# 8HA.net
KiCad netlist of a schematic drawn in EAGLE
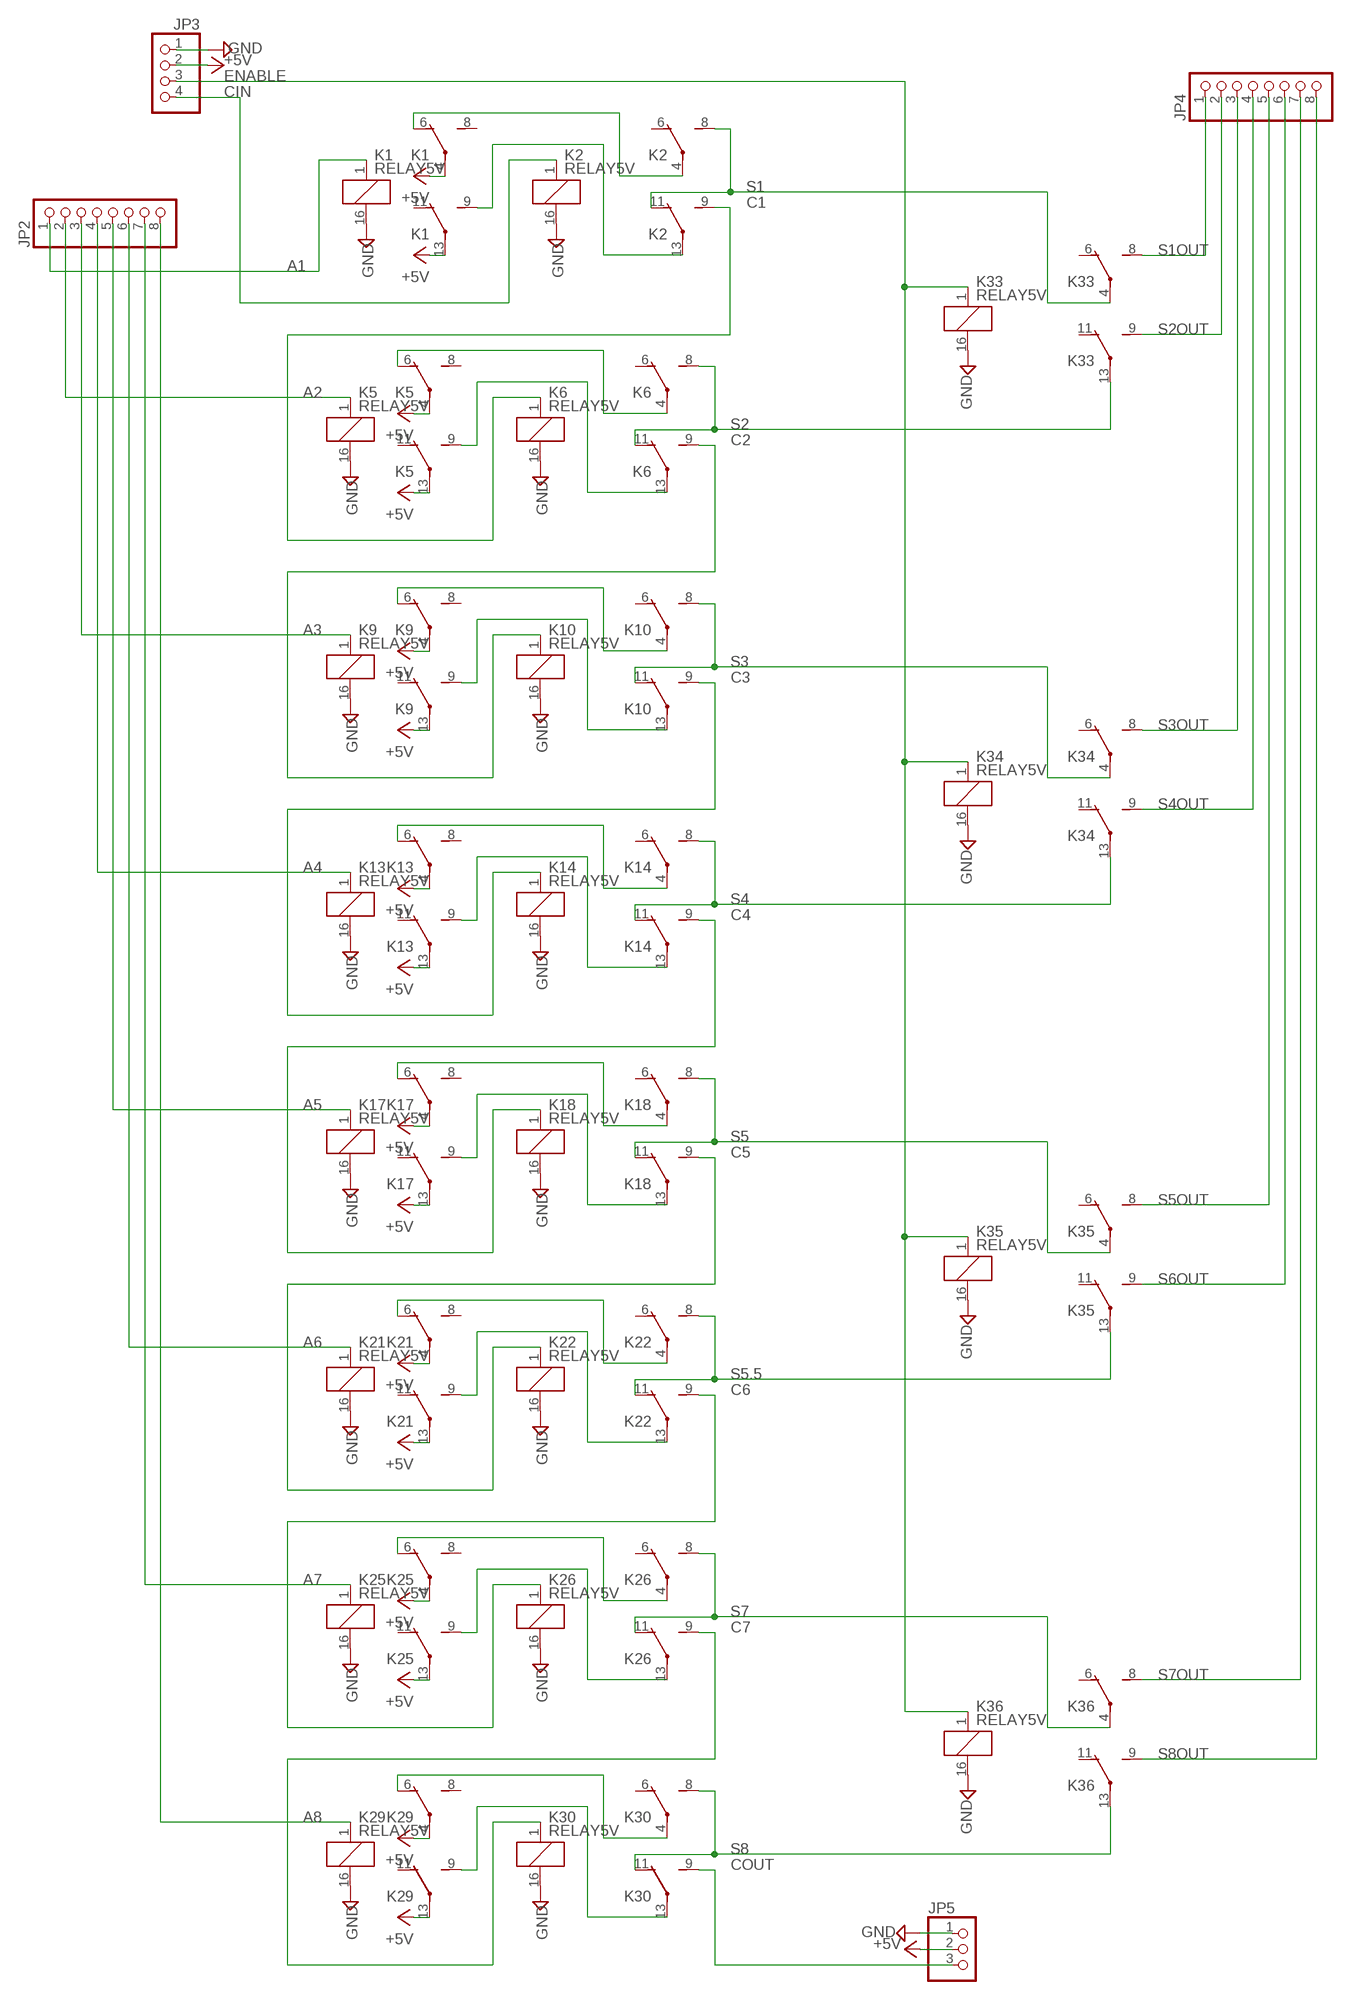
[diagram p0: schematic, sheet 1]

(export (version "E")
  (design (tool "Eeschema 10.0.6"))
  (components
    (comp (ref "JP2")
      (value "PINHD-1X8")
      (footprint "eagle-import:1X08")
      (libsource (lib "eagle-import") (part "PINHD-1X8"))
    )
    (comp (ref "JP3")
      (value "PINHD-1X4")
      (footprint "eagle-import:1X04")
      (libsource (lib "eagle-import") (part "PINHD-1X4"))
    )
    (comp (ref "JP4")
      (value "PINHD-1X8")
      (footprint "eagle-import:1X08")
      (libsource (lib "eagle-import") (part "PINHD-1X8"))
    )
    (comp (ref "JP5")
      (value "PINHD-1X3")
      (footprint "eagle-import:1X03")
      (libsource (lib "eagle-import") (part "PINHD-1X3"))
    )
    (comp (ref "K1")
      (value "RELAY5V")
      (footprint "eagle-import:DS-BT")
      (libsource (lib "eagle-import") (part "RELAY5V"))
    )
    (comp (ref "K2")
      (value "RELAY5V")
      (footprint "eagle-import:DS-BT")
      (libsource (lib "eagle-import") (part "RELAY5V"))
    )
    (comp (ref "K5")
      (value "RELAY5V")
      (footprint "eagle-import:DS-BT")
      (libsource (lib "eagle-import") (part "RELAY5V"))
    )
    (comp (ref "K6")
      (value "RELAY5V")
      (footprint "eagle-import:DS-BT")
      (libsource (lib "eagle-import") (part "RELAY5V"))
    )
    (comp (ref "K9")
      (value "RELAY5V")
      (footprint "eagle-import:DS-BT")
      (libsource (lib "eagle-import") (part "RELAY5V"))
    )
    (comp (ref "K10")
      (value "RELAY5V")
      (footprint "eagle-import:DS-BT")
      (libsource (lib "eagle-import") (part "RELAY5V"))
    )
    (comp (ref "K13")
      (value "RELAY5V")
      (footprint "eagle-import:DS-BT")
      (libsource (lib "eagle-import") (part "RELAY5V"))
    )
    (comp (ref "K14")
      (value "RELAY5V")
      (footprint "eagle-import:DS-BT")
      (libsource (lib "eagle-import") (part "RELAY5V"))
    )
    (comp (ref "K17")
      (value "RELAY5V")
      (footprint "eagle-import:DS-BT")
      (libsource (lib "eagle-import") (part "RELAY5V"))
    )
    (comp (ref "K18")
      (value "RELAY5V")
      (footprint "eagle-import:DS-BT")
      (libsource (lib "eagle-import") (part "RELAY5V"))
    )
    (comp (ref "K21")
      (value "RELAY5V")
      (footprint "eagle-import:DS-BT")
      (libsource (lib "eagle-import") (part "RELAY5V"))
    )
    (comp (ref "K22")
      (value "RELAY5V")
      (footprint "eagle-import:DS-BT")
      (libsource (lib "eagle-import") (part "RELAY5V"))
    )
    (comp (ref "K25")
      (value "RELAY5V")
      (footprint "eagle-import:DS-BT")
      (libsource (lib "eagle-import") (part "RELAY5V"))
    )
    (comp (ref "K26")
      (value "RELAY5V")
      (footprint "eagle-import:DS-BT")
      (libsource (lib "eagle-import") (part "RELAY5V"))
    )
    (comp (ref "K29")
      (value "RELAY5V")
      (footprint "eagle-import:DS-BT")
      (libsource (lib "eagle-import") (part "RELAY5V"))
    )
    (comp (ref "K30")
      (value "RELAY5V")
      (footprint "eagle-import:DS-BT")
      (libsource (lib "eagle-import") (part "RELAY5V"))
    )
    (comp (ref "K33")
      (value "RELAY5V")
      (footprint "eagle-import:DS-BT")
      (libsource (lib "eagle-import") (part "RELAY5V"))
    )
    (comp (ref "K34")
      (value "RELAY5V")
      (footprint "eagle-import:DS-BT")
      (libsource (lib "eagle-import") (part "RELAY5V"))
    )
    (comp (ref "K35")
      (value "RELAY5V")
      (footprint "eagle-import:DS-BT")
      (libsource (lib "eagle-import") (part "RELAY5V"))
    )
    (comp (ref "K36")
      (value "RELAY5V")
      (footprint "eagle-import:DS-BT")
      (libsource (lib "eagle-import") (part "RELAY5V"))
    )
  )
  (nets
    (net (code "1") (name "+5V") (class "Default")
      (node (ref "JP3") (pin "2") (pinfunction "2_2") (pintype "passive"))
      (node (ref "JP5") (pin "2") (pinfunction "2_2") (pintype "passive"))
      (node (ref "K1") (pin "13") (pinfunction "P_13") (pintype "passive"))
      (node (ref "K1") (pin "4") (pinfunction "P_4") (pintype "passive"))
      (node (ref "K13") (pin "13") (pinfunction "P_13") (pintype "passive"))
      (node (ref "K13") (pin "4") (pinfunction "P_4") (pintype "passive"))
      (node (ref "K17") (pin "13") (pinfunction "P_13") (pintype "passive"))
      (node (ref "K17") (pin "4") (pinfunction "P_4") (pintype "passive"))
      (node (ref "K21") (pin "13") (pinfunction "P_13") (pintype "passive"))
      (node (ref "K21") (pin "4") (pinfunction "P_4") (pintype "passive"))
      (node (ref "K25") (pin "13") (pinfunction "P_13") (pintype "passive"))
      (node (ref "K25") (pin "4") (pinfunction "P_4") (pintype "passive"))
      (node (ref "K29") (pin "13") (pinfunction "P_13") (pintype "passive"))
      (node (ref "K29") (pin "4") (pinfunction "P_4") (pintype "passive"))
      (node (ref "K5") (pin "13") (pinfunction "P_13") (pintype "passive"))
      (node (ref "K5") (pin "4") (pinfunction "P_4") (pintype "passive"))
      (node (ref "K9") (pin "13") (pinfunction "P_13") (pintype "passive"))
      (node (ref "K9") (pin "4") (pinfunction "P_4") (pintype "passive"))
    )
    (net (code "2") (name "/A1") (class "Default")
      (node (ref "JP2") (pin "1") (pinfunction "1_1") (pintype "passive"))
      (node (ref "K1") (pin "1") (pinfunction "+_1") (pintype "passive"))
    )
    (net (code "3") (name "/A2") (class "Default")
      (node (ref "JP2") (pin "2") (pinfunction "2_2") (pintype "passive"))
      (node (ref "K5") (pin "1") (pinfunction "+_1") (pintype "passive"))
    )
    (net (code "4") (name "/A3") (class "Default")
      (node (ref "JP2") (pin "3") (pinfunction "3_3") (pintype "passive"))
      (node (ref "K9") (pin "1") (pinfunction "+_1") (pintype "passive"))
    )
    (net (code "5") (name "/A4") (class "Default")
      (node (ref "JP2") (pin "4") (pinfunction "4_4") (pintype "passive"))
      (node (ref "K13") (pin "1") (pinfunction "+_1") (pintype "passive"))
    )
    (net (code "6") (name "/A5") (class "Default")
      (node (ref "JP2") (pin "5") (pinfunction "5_5") (pintype "passive"))
      (node (ref "K17") (pin "1") (pinfunction "+_1") (pintype "passive"))
    )
    (net (code "7") (name "/A6") (class "Default")
      (node (ref "JP2") (pin "6") (pinfunction "6_6") (pintype "passive"))
      (node (ref "K21") (pin "1") (pinfunction "+_1") (pintype "passive"))
    )
    (net (code "8") (name "/A7") (class "Default")
      (node (ref "JP2") (pin "7") (pinfunction "7_7") (pintype "passive"))
      (node (ref "K25") (pin "1") (pinfunction "+_1") (pintype "passive"))
    )
    (net (code "9") (name "/A8") (class "Default")
      (node (ref "JP2") (pin "8") (pinfunction "8_8") (pintype "passive"))
      (node (ref "K29") (pin "1") (pinfunction "+_1") (pintype "passive"))
    )
    (net (code "10") (name "/C1") (class "Default")
      (node (ref "K2") (pin "9") (pinfunction "S_9") (pintype "passive"))
      (node (ref "K6") (pin "1") (pinfunction "+_1") (pintype "passive"))
    )
    (net (code "11") (name "/C2") (class "Default")
      (node (ref "K10") (pin "1") (pinfunction "+_1") (pintype "passive"))
      (node (ref "K6") (pin "9") (pinfunction "S_9") (pintype "passive"))
    )
    (net (code "12") (name "/C3") (class "Default")
      (node (ref "K10") (pin "9") (pinfunction "S_9") (pintype "passive"))
      (node (ref "K14") (pin "1") (pinfunction "+_1") (pintype "passive"))
    )
    (net (code "13") (name "/C4") (class "Default")
      (node (ref "K14") (pin "9") (pinfunction "S_9") (pintype "passive"))
      (node (ref "K18") (pin "1") (pinfunction "+_1") (pintype "passive"))
    )
    (net (code "14") (name "/C5") (class "Default")
      (node (ref "K18") (pin "9") (pinfunction "S_9") (pintype "passive"))
      (node (ref "K22") (pin "1") (pinfunction "+_1") (pintype "passive"))
    )
    (net (code "15") (name "/C6") (class "Default")
      (node (ref "K22") (pin "9") (pinfunction "S_9") (pintype "passive"))
      (node (ref "K26") (pin "1") (pinfunction "+_1") (pintype "passive"))
    )
    (net (code "16") (name "/C7") (class "Default")
      (node (ref "K26") (pin "9") (pinfunction "S_9") (pintype "passive"))
      (node (ref "K30") (pin "1") (pinfunction "+_1") (pintype "passive"))
    )
    (net (code "17") (name "/CIN") (class "Default")
      (node (ref "JP3") (pin "4") (pinfunction "4_4") (pintype "passive"))
      (node (ref "K2") (pin "1") (pinfunction "+_1") (pintype "passive"))
    )
    (net (code "18") (name "/COUT") (class "Default")
      (node (ref "JP5") (pin "3") (pinfunction "3_3") (pintype "passive"))
      (node (ref "K30") (pin "9") (pinfunction "S_9") (pintype "passive"))
    )
    (net (code "19") (name "/ENABLE") (class "Default")
      (node (ref "JP3") (pin "3") (pinfunction "3_3") (pintype "passive"))
      (node (ref "K33") (pin "1") (pinfunction "+_1") (pintype "passive"))
      (node (ref "K34") (pin "1") (pinfunction "+_1") (pintype "passive"))
      (node (ref "K35") (pin "1") (pinfunction "+_1") (pintype "passive"))
      (node (ref "K36") (pin "1") (pinfunction "+_1") (pintype "passive"))
    )
    (net (code "20") (name "/S1") (class "Default")
      (node (ref "K2") (pin "11") (pinfunction "O_11") (pintype "passive"))
      (node (ref "K2") (pin "8") (pinfunction "S_8") (pintype "passive"))
      (node (ref "K33") (pin "4") (pinfunction "P_4") (pintype "passive"))
    )
    (net (code "21") (name "/S1OUT") (class "Default")
      (node (ref "JP4") (pin "1") (pinfunction "1_1") (pintype "passive"))
      (node (ref "K33") (pin "8") (pinfunction "S_8") (pintype "passive"))
    )
    (net (code "22") (name "/S2") (class "Default")
      (node (ref "K33") (pin "13") (pinfunction "P_13") (pintype "passive"))
      (node (ref "K6") (pin "11") (pinfunction "O_11") (pintype "passive"))
      (node (ref "K6") (pin "8") (pinfunction "S_8") (pintype "passive"))
    )
    (net (code "23") (name "/S2OUT") (class "Default")
      (node (ref "JP4") (pin "2") (pinfunction "2_2") (pintype "passive"))
      (node (ref "K33") (pin "9") (pinfunction "S_9") (pintype "passive"))
    )
    (net (code "24") (name "/S3") (class "Default")
      (node (ref "K10") (pin "11") (pinfunction "O_11") (pintype "passive"))
      (node (ref "K10") (pin "8") (pinfunction "S_8") (pintype "passive"))
      (node (ref "K34") (pin "4") (pinfunction "P_4") (pintype "passive"))
    )
    (net (code "25") (name "/S3OUT") (class "Default")
      (node (ref "JP4") (pin "3") (pinfunction "3_3") (pintype "passive"))
      (node (ref "K34") (pin "8") (pinfunction "S_8") (pintype "passive"))
    )
    (net (code "26") (name "/S4") (class "Default")
      (node (ref "K14") (pin "11") (pinfunction "O_11") (pintype "passive"))
      (node (ref "K14") (pin "8") (pinfunction "S_8") (pintype "passive"))
      (node (ref "K34") (pin "13") (pinfunction "P_13") (pintype "passive"))
    )
    (net (code "27") (name "/S4OUT") (class "Default")
      (node (ref "JP4") (pin "4") (pinfunction "4_4") (pintype "passive"))
      (node (ref "K34") (pin "9") (pinfunction "S_9") (pintype "passive"))
    )
    (net (code "28") (name "/S5") (class "Default")
      (node (ref "K18") (pin "11") (pinfunction "O_11") (pintype "passive"))
      (node (ref "K18") (pin "8") (pinfunction "S_8") (pintype "passive"))
      (node (ref "K35") (pin "4") (pinfunction "P_4") (pintype "passive"))
    )
    (net (code "29") (name "/S5.5") (class "Default")
      (node (ref "K22") (pin "11") (pinfunction "O_11") (pintype "passive"))
      (node (ref "K22") (pin "8") (pinfunction "S_8") (pintype "passive"))
      (node (ref "K35") (pin "13") (pinfunction "P_13") (pintype "passive"))
    )
    (net (code "30") (name "/S5OUT") (class "Default")
      (node (ref "JP4") (pin "5") (pinfunction "5_5") (pintype "passive"))
      (node (ref "K35") (pin "8") (pinfunction "S_8") (pintype "passive"))
    )
    (net (code "31") (name "/S6OUT") (class "Default")
      (node (ref "JP4") (pin "6") (pinfunction "6_6") (pintype "passive"))
      (node (ref "K35") (pin "9") (pinfunction "S_9") (pintype "passive"))
    )
    (net (code "32") (name "/S7") (class "Default")
      (node (ref "K26") (pin "11") (pinfunction "O_11") (pintype "passive"))
      (node (ref "K26") (pin "8") (pinfunction "S_8") (pintype "passive"))
      (node (ref "K36") (pin "4") (pinfunction "P_4") (pintype "passive"))
    )
    (net (code "33") (name "/S7OUT") (class "Default")
      (node (ref "JP4") (pin "7") (pinfunction "7_7") (pintype "passive"))
      (node (ref "K36") (pin "8") (pinfunction "S_8") (pintype "passive"))
    )
    (net (code "34") (name "/S8") (class "Default")
      (node (ref "K30") (pin "11") (pinfunction "O_11") (pintype "passive"))
      (node (ref "K30") (pin "8") (pinfunction "S_8") (pintype "passive"))
      (node (ref "K36") (pin "13") (pinfunction "P_13") (pintype "passive"))
    )
    (net (code "35") (name "/S8OUT") (class "Default")
      (node (ref "JP4") (pin "8") (pinfunction "8_8") (pintype "passive"))
      (node (ref "K36") (pin "9") (pinfunction "S_9") (pintype "passive"))
    )
    (net (code "36") (name "GND") (class "Default")
      (node (ref "JP3") (pin "1") (pinfunction "1_1") (pintype "passive"))
      (node (ref "JP5") (pin "1") (pinfunction "1_1") (pintype "passive"))
      (node (ref "K1") (pin "16") (pinfunction "-_16") (pintype "passive"))
      (node (ref "K10") (pin "16") (pinfunction "-_16") (pintype "passive"))
      (node (ref "K13") (pin "16") (pinfunction "-_16") (pintype "passive"))
      (node (ref "K14") (pin "16") (pinfunction "-_16") (pintype "passive"))
      (node (ref "K17") (pin "16") (pinfunction "-_16") (pintype "passive"))
      (node (ref "K18") (pin "16") (pinfunction "-_16") (pintype "passive"))
      (node (ref "K2") (pin "16") (pinfunction "-_16") (pintype "passive"))
      (node (ref "K21") (pin "16") (pinfunction "-_16") (pintype "passive"))
      (node (ref "K22") (pin "16") (pinfunction "-_16") (pintype "passive"))
      (node (ref "K25") (pin "16") (pinfunction "-_16") (pintype "passive"))
      (node (ref "K26") (pin "16") (pinfunction "-_16") (pintype "passive"))
      (node (ref "K29") (pin "16") (pinfunction "-_16") (pintype "passive"))
      (node (ref "K30") (pin "16") (pinfunction "-_16") (pintype "passive"))
      (node (ref "K33") (pin "16") (pinfunction "-_16") (pintype "passive"))
      (node (ref "K34") (pin "16") (pinfunction "-_16") (pintype "passive"))
      (node (ref "K35") (pin "16") (pinfunction "-_16") (pintype "passive"))
      (node (ref "K36") (pin "16") (pinfunction "-_16") (pintype "passive"))
      (node (ref "K5") (pin "16") (pinfunction "-_16") (pintype "passive"))
      (node (ref "K6") (pin "16") (pinfunction "-_16") (pintype "passive"))
      (node (ref "K9") (pin "16") (pinfunction "-_16") (pintype "passive"))
    )
    (net (code "37") (name "Net-(K1B-O)") (class "Default")
      (node (ref "K1") (pin "6") (pinfunction "O_6") (pintype "passive"))
      (node (ref "K2") (pin "4") (pinfunction "P_4") (pintype "passive"))
    )
    (net (code "38") (name "Net-(K1C-S)") (class "Default")
      (node (ref "K1") (pin "9") (pinfunction "S_9") (pintype "passive"))
      (node (ref "K2") (pin "13") (pinfunction "P_13") (pintype "passive"))
    )
    (net (code "39") (name "Net-(K5B-O)") (class "Default")
      (node (ref "K5") (pin "6") (pinfunction "O_6") (pintype "passive"))
      (node (ref "K6") (pin "4") (pinfunction "P_4") (pintype "passive"))
    )
    (net (code "40") (name "Net-(K5C-S)") (class "Default")
      (node (ref "K5") (pin "9") (pinfunction "S_9") (pintype "passive"))
      (node (ref "K6") (pin "13") (pinfunction "P_13") (pintype "passive"))
    )
    (net (code "41") (name "Net-(K10B-P)") (class "Default")
      (node (ref "K10") (pin "4") (pinfunction "P_4") (pintype "passive"))
      (node (ref "K9") (pin "6") (pinfunction "O_6") (pintype "passive"))
    )
    (net (code "42") (name "Net-(K10C-P)") (class "Default")
      (node (ref "K10") (pin "13") (pinfunction "P_13") (pintype "passive"))
      (node (ref "K9") (pin "9") (pinfunction "S_9") (pintype "passive"))
    )
    (net (code "43") (name "Net-(K13B-O)") (class "Default")
      (node (ref "K13") (pin "6") (pinfunction "O_6") (pintype "passive"))
      (node (ref "K14") (pin "4") (pinfunction "P_4") (pintype "passive"))
    )
    (net (code "44") (name "Net-(K13C-S)") (class "Default")
      (node (ref "K13") (pin "9") (pinfunction "S_9") (pintype "passive"))
      (node (ref "K14") (pin "13") (pinfunction "P_13") (pintype "passive"))
    )
    (net (code "45") (name "Net-(K17B-O)") (class "Default")
      (node (ref "K17") (pin "6") (pinfunction "O_6") (pintype "passive"))
      (node (ref "K18") (pin "4") (pinfunction "P_4") (pintype "passive"))
    )
    (net (code "46") (name "Net-(K17C-S)") (class "Default")
      (node (ref "K17") (pin "9") (pinfunction "S_9") (pintype "passive"))
      (node (ref "K18") (pin "13") (pinfunction "P_13") (pintype "passive"))
    )
    (net (code "47") (name "Net-(K21B-O)") (class "Default")
      (node (ref "K21") (pin "6") (pinfunction "O_6") (pintype "passive"))
      (node (ref "K22") (pin "4") (pinfunction "P_4") (pintype "passive"))
    )
    (net (code "48") (name "Net-(K21C-S)") (class "Default")
      (node (ref "K21") (pin "9") (pinfunction "S_9") (pintype "passive"))
      (node (ref "K22") (pin "13") (pinfunction "P_13") (pintype "passive"))
    )
    (net (code "49") (name "Net-(K25B-O)") (class "Default")
      (node (ref "K25") (pin "6") (pinfunction "O_6") (pintype "passive"))
      (node (ref "K26") (pin "4") (pinfunction "P_4") (pintype "passive"))
    )
    (net (code "50") (name "Net-(K25C-S)") (class "Default")
      (node (ref "K25") (pin "9") (pinfunction "S_9") (pintype "passive"))
      (node (ref "K26") (pin "13") (pinfunction "P_13") (pintype "passive"))
    )
    (net (code "51") (name "Net-(K29B-O)") (class "Default")
      (node (ref "K29") (pin "6") (pinfunction "O_6") (pintype "passive"))
      (node (ref "K30") (pin "4") (pinfunction "P_4") (pintype "passive"))
    )
    (net (code "52") (name "Net-(K29C-S)") (class "Default")
      (node (ref "K29") (pin "9") (pinfunction "S_9") (pintype "passive"))
      (node (ref "K30") (pin "13") (pinfunction "P_13") (pintype "passive"))
    )
    (net (code "53") (name "unconnected-(K1B-S-Pad8)") (class "Default")
      (node (ref "K1") (pin "8") (pinfunction "S_8") (pintype "passive"))
    )
    (net (code "54") (name "unconnected-(K1C-O-Pad11)") (class "Default")
      (node (ref "K1") (pin "11") (pinfunction "O_11") (pintype "passive"))
    )
    (net (code "55") (name "unconnected-(K2B-O-Pad6)") (class "Default")
      (node (ref "K2") (pin "6") (pinfunction "O_6") (pintype "passive"))
    )
    (net (code "56") (name "unconnected-(K5B-S-Pad8)") (class "Default")
      (node (ref "K5") (pin "8") (pinfunction "S_8") (pintype "passive"))
    )
    (net (code "57") (name "unconnected-(K5C-O-Pad11)") (class "Default")
      (node (ref "K5") (pin "11") (pinfunction "O_11") (pintype "passive"))
    )
    (net (code "58") (name "unconnected-(K6B-O-Pad6)") (class "Default")
      (node (ref "K6") (pin "6") (pinfunction "O_6") (pintype "passive"))
    )
    (net (code "59") (name "unconnected-(K9B-S-Pad8)") (class "Default")
      (node (ref "K9") (pin "8") (pinfunction "S_8") (pintype "passive"))
    )
    (net (code "60") (name "unconnected-(K9C-O-Pad11)") (class "Default")
      (node (ref "K9") (pin "11") (pinfunction "O_11") (pintype "passive"))
    )
    (net (code "61") (name "unconnected-(K10B-O-Pad6)") (class "Default")
      (node (ref "K10") (pin "6") (pinfunction "O_6") (pintype "passive"))
    )
    (net (code "62") (name "unconnected-(K13B-S-Pad8)") (class "Default")
      (node (ref "K13") (pin "8") (pinfunction "S_8") (pintype "passive"))
    )
    (net (code "63") (name "unconnected-(K13C-O-Pad11)") (class "Default")
      (node (ref "K13") (pin "11") (pinfunction "O_11") (pintype "passive"))
    )
    (net (code "64") (name "unconnected-(K14B-O-Pad6)") (class "Default")
      (node (ref "K14") (pin "6") (pinfunction "O_6") (pintype "passive"))
    )
    (net (code "65") (name "unconnected-(K17B-S-Pad8)") (class "Default")
      (node (ref "K17") (pin "8") (pinfunction "S_8") (pintype "passive"))
    )
    (net (code "66") (name "unconnected-(K17C-O-Pad11)") (class "Default")
      (node (ref "K17") (pin "11") (pinfunction "O_11") (pintype "passive"))
    )
    (net (code "67") (name "unconnected-(K18B-O-Pad6)") (class "Default")
      (node (ref "K18") (pin "6") (pinfunction "O_6") (pintype "passive"))
    )
    (net (code "68") (name "unconnected-(K21B-S-Pad8)") (class "Default")
      (node (ref "K21") (pin "8") (pinfunction "S_8") (pintype "passive"))
    )
    (net (code "69") (name "unconnected-(K21C-O-Pad11)") (class "Default")
      (node (ref "K21") (pin "11") (pinfunction "O_11") (pintype "passive"))
    )
    (net (code "70") (name "unconnected-(K22B-O-Pad6)") (class "Default")
      (node (ref "K22") (pin "6") (pinfunction "O_6") (pintype "passive"))
    )
    (net (code "71") (name "unconnected-(K25B-S-Pad8)") (class "Default")
      (node (ref "K25") (pin "8") (pinfunction "S_8") (pintype "passive"))
    )
    (net (code "72") (name "unconnected-(K25C-O-Pad11)") (class "Default")
      (node (ref "K25") (pin "11") (pinfunction "O_11") (pintype "passive"))
    )
    (net (code "73") (name "unconnected-(K26B-O-Pad6)") (class "Default")
      (node (ref "K26") (pin "6") (pinfunction "O_6") (pintype "passive"))
    )
    (net (code "74") (name "unconnected-(K29B-S-Pad8)") (class "Default")
      (node (ref "K29") (pin "8") (pinfunction "S_8") (pintype "passive"))
    )
    (net (code "75") (name "unconnected-(K29C-O-Pad11)") (class "Default")
      (node (ref "K29") (pin "11") (pinfunction "O_11") (pintype "passive"))
    )
    (net (code "76") (name "unconnected-(K30B-O-Pad6)") (class "Default")
      (node (ref "K30") (pin "6") (pinfunction "O_6") (pintype "passive"))
    )
    (net (code "77") (name "unconnected-(K33B-O-Pad6)") (class "Default")
      (node (ref "K33") (pin "6") (pinfunction "O_6") (pintype "passive"))
    )
    (net (code "78") (name "unconnected-(K33C-O-Pad11)") (class "Default")
      (node (ref "K33") (pin "11") (pinfunction "O_11") (pintype "passive"))
    )
    (net (code "79") (name "unconnected-(K34B-O-Pad6)") (class "Default")
      (node (ref "K34") (pin "6") (pinfunction "O_6") (pintype "passive"))
    )
    (net (code "80") (name "unconnected-(K34C-O-Pad11)") (class "Default")
      (node (ref "K34") (pin "11") (pinfunction "O_11") (pintype "passive"))
    )
    (net (code "81") (name "unconnected-(K35B-O-Pad6)") (class "Default")
      (node (ref "K35") (pin "6") (pinfunction "O_6") (pintype "passive"))
    )
    (net (code "82") (name "unconnected-(K35C-O-Pad11)") (class "Default")
      (node (ref "K35") (pin "11") (pinfunction "O_11") (pintype "passive"))
    )
    (net (code "83") (name "unconnected-(K36B-O-Pad6)") (class "Default")
      (node (ref "K36") (pin "6") (pinfunction "O_6") (pintype "passive"))
    )
    (net (code "84") (name "unconnected-(K36C-O-Pad11)") (class "Default")
      (node (ref "K36") (pin "11") (pinfunction "O_11") (pintype "passive"))
    )
  )
)
